# mt15_n.net
KiCad netlist of a schematic drawn in EAGLE
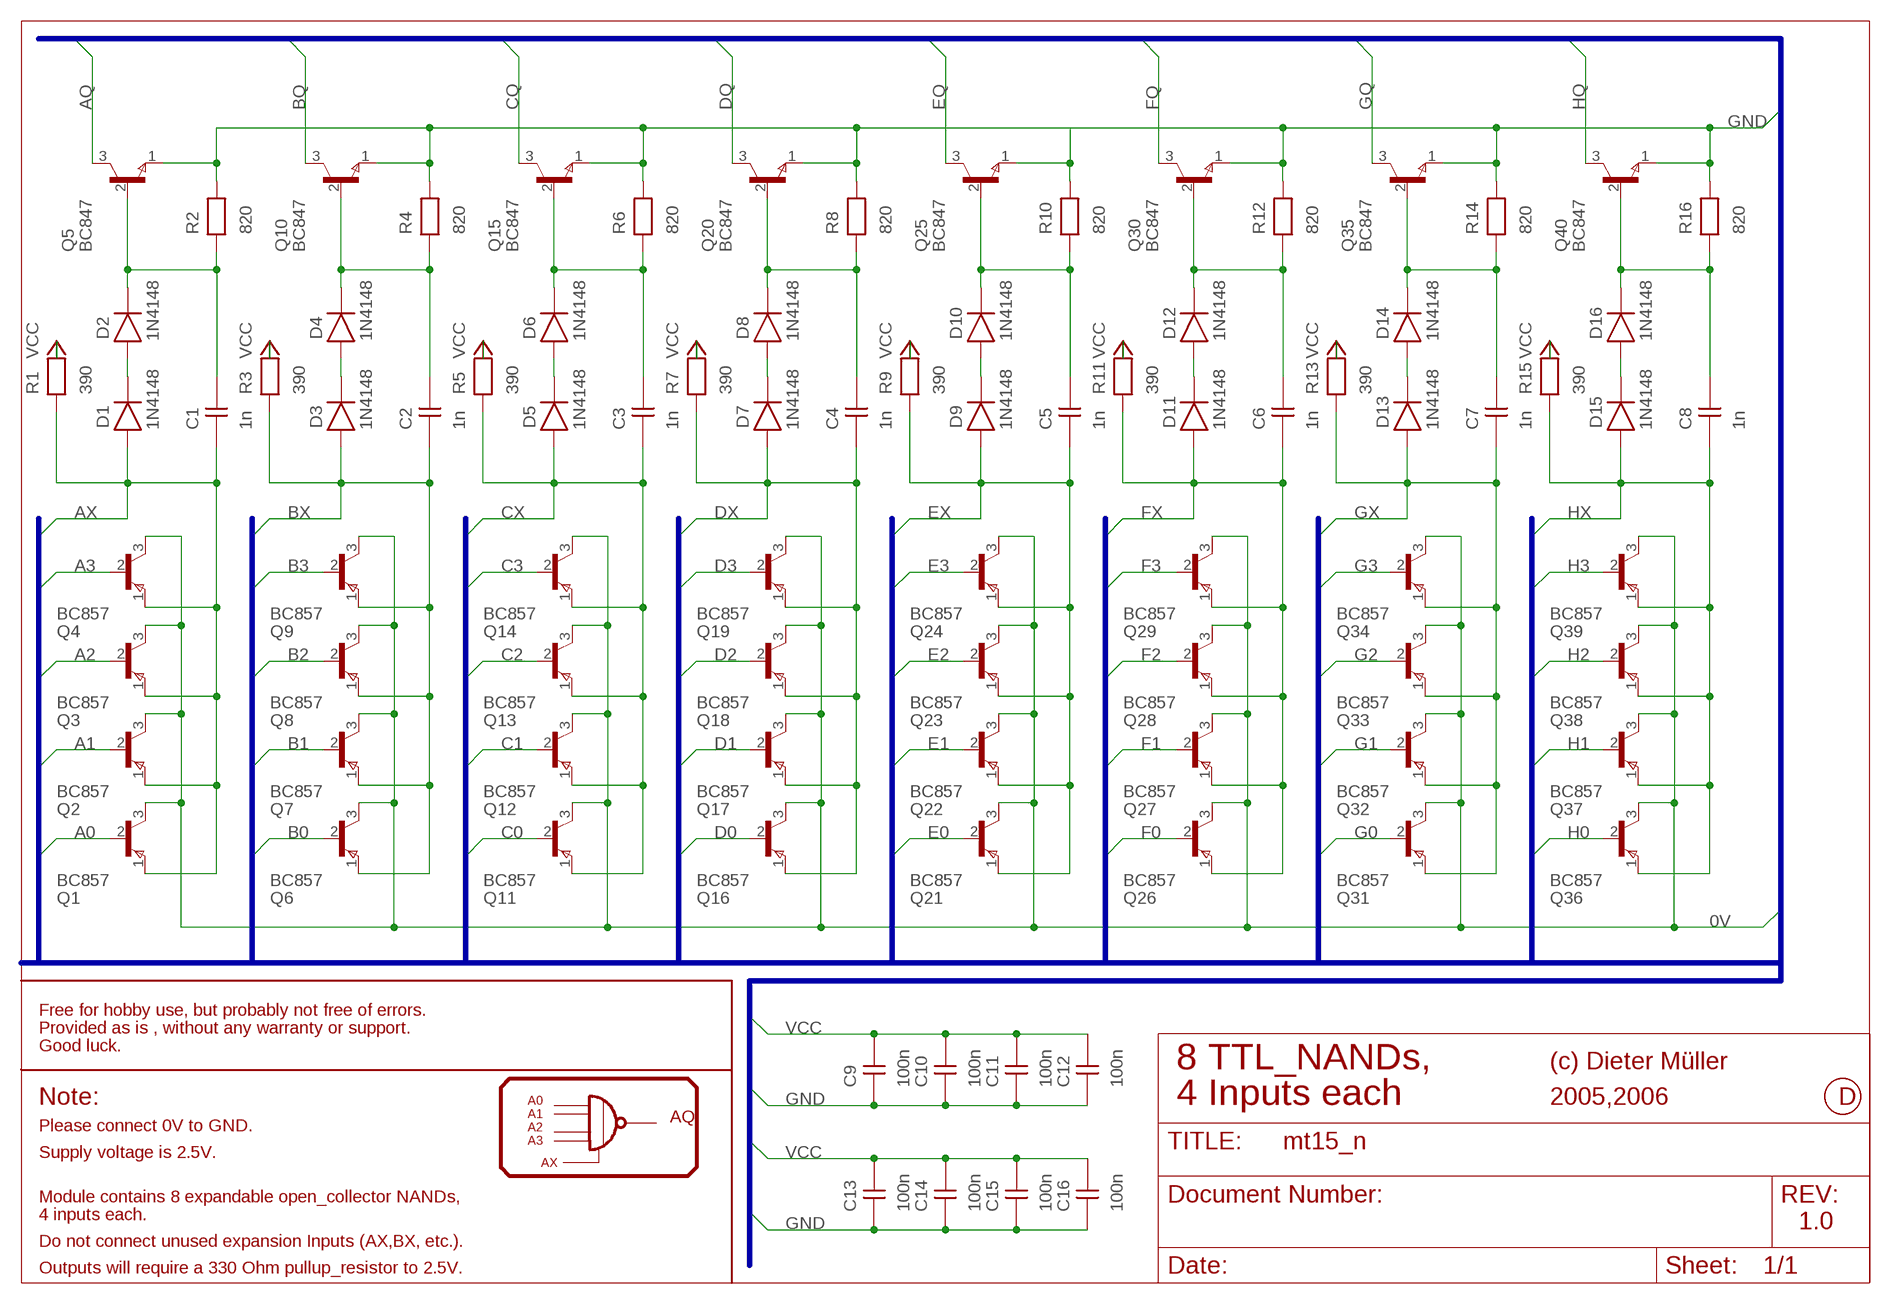
[diagram p0: schematic, sheet 1]

(export (version "E")
  (design (tool "Eeschema 10.0.6"))
  (components
    (comp (ref "C1")
      (value "1n")
      (footprint "eagle-import:0204")
      (libsource (lib "eagle-import") (part "CAPNP-5@2"))
    )
    (comp (ref "C2")
      (value "1n")
      (footprint "eagle-import:0204")
      (libsource (lib "eagle-import") (part "CAPNP-5@2"))
    )
    (comp (ref "C3")
      (value "1n")
      (footprint "eagle-import:0204")
      (libsource (lib "eagle-import") (part "CAPNP-5@2"))
    )
    (comp (ref "C4")
      (value "1n")
      (footprint "eagle-import:0204")
      (libsource (lib "eagle-import") (part "CAPNP-5@2"))
    )
    (comp (ref "C5")
      (value "1n")
      (footprint "eagle-import:0204")
      (libsource (lib "eagle-import") (part "CAPNP-5@2"))
    )
    (comp (ref "C6")
      (value "1n")
      (footprint "eagle-import:0204")
      (libsource (lib "eagle-import") (part "CAPNP-5@2"))
    )
    (comp (ref "C7")
      (value "1n")
      (footprint "eagle-import:0204")
      (libsource (lib "eagle-import") (part "CAPNP-5@2"))
    )
    (comp (ref "C8")
      (value "1n")
      (footprint "eagle-import:0204")
      (libsource (lib "eagle-import") (part "CAPNP-5@2"))
    )
    (comp (ref "C9")
      (value "100n")
      (footprint "eagle-import:0204")
      (libsource (lib "eagle-import") (part "CAPNP-5@2"))
    )
    (comp (ref "C10")
      (value "100n")
      (footprint "eagle-import:0204")
      (libsource (lib "eagle-import") (part "CAPNP-5@2"))
    )
    (comp (ref "C11")
      (value "100n")
      (footprint "eagle-import:0204")
      (libsource (lib "eagle-import") (part "CAPNP-5@2"))
    )
    (comp (ref "C12")
      (value "100n")
      (footprint "eagle-import:0204")
      (libsource (lib "eagle-import") (part "CAPNP-5@2"))
    )
    (comp (ref "C13")
      (value "100n")
      (footprint "eagle-import:0204")
      (libsource (lib "eagle-import") (part "CAPNP-5@2"))
    )
    (comp (ref "C14")
      (value "100n")
      (footprint "eagle-import:0204")
      (libsource (lib "eagle-import") (part "CAPNP-5@2"))
    )
    (comp (ref "C15")
      (value "100n")
      (footprint "eagle-import:0204")
      (libsource (lib "eagle-import") (part "CAPNP-5@2"))
    )
    (comp (ref "C16")
      (value "100n")
      (footprint "eagle-import:0204")
      (libsource (lib "eagle-import") (part "CAPNP-5@2"))
    )
    (comp (ref "D1")
      (value "1N4148")
      (footprint "eagle-import:0204D")
      (libsource (lib "eagle-import") (part "DIODE-7,5@2"))
    )
    (comp (ref "D2")
      (value "1N4148")
      (footprint "eagle-import:0204D")
      (libsource (lib "eagle-import") (part "DIODE-7,5@2"))
    )
    (comp (ref "D3")
      (value "1N4148")
      (footprint "eagle-import:0204D")
      (libsource (lib "eagle-import") (part "DIODE-7,5@2"))
    )
    (comp (ref "D4")
      (value "1N4148")
      (footprint "eagle-import:0204D")
      (libsource (lib "eagle-import") (part "DIODE-7,5@2"))
    )
    (comp (ref "D5")
      (value "1N4148")
      (footprint "eagle-import:0204D")
      (libsource (lib "eagle-import") (part "DIODE-7,5@2"))
    )
    (comp (ref "D6")
      (value "1N4148")
      (footprint "eagle-import:0204D")
      (libsource (lib "eagle-import") (part "DIODE-7,5@2"))
    )
    (comp (ref "D7")
      (value "1N4148")
      (footprint "eagle-import:0204D")
      (libsource (lib "eagle-import") (part "DIODE-7,5@2"))
    )
    (comp (ref "D8")
      (value "1N4148")
      (footprint "eagle-import:0204D")
      (libsource (lib "eagle-import") (part "DIODE-7,5@2"))
    )
    (comp (ref "D9")
      (value "1N4148")
      (footprint "eagle-import:0204D")
      (libsource (lib "eagle-import") (part "DIODE-7,5@2"))
    )
    (comp (ref "D10")
      (value "1N4148")
      (footprint "eagle-import:0204D")
      (libsource (lib "eagle-import") (part "DIODE-7,5@2"))
    )
    (comp (ref "D11")
      (value "1N4148")
      (footprint "eagle-import:0204D")
      (libsource (lib "eagle-import") (part "DIODE-7,5@2"))
    )
    (comp (ref "D12")
      (value "1N4148")
      (footprint "eagle-import:0204D")
      (libsource (lib "eagle-import") (part "DIODE-7,5@2"))
    )
    (comp (ref "D13")
      (value "1N4148")
      (footprint "eagle-import:0204D")
      (libsource (lib "eagle-import") (part "DIODE-7,5@2"))
    )
    (comp (ref "D14")
      (value "1N4148")
      (footprint "eagle-import:0204D")
      (libsource (lib "eagle-import") (part "DIODE-7,5@2"))
    )
    (comp (ref "D15")
      (value "1N4148")
      (footprint "eagle-import:0204D")
      (libsource (lib "eagle-import") (part "DIODE-7,5@2"))
    )
    (comp (ref "D16")
      (value "1N4148")
      (footprint "eagle-import:0204D")
      (libsource (lib "eagle-import") (part "DIODE-7,5@2"))
    )
    (comp (ref "Q1")
      (value "BC857")
      (footprint "eagle-import:SOT-23")
      (libsource (lib "eagle-import") (part "BC557@2"))
    )
    (comp (ref "Q2")
      (value "BC857")
      (footprint "eagle-import:SOT-23")
      (libsource (lib "eagle-import") (part "BC557@2"))
    )
    (comp (ref "Q3")
      (value "BC857")
      (footprint "eagle-import:SOT-23")
      (libsource (lib "eagle-import") (part "BC557@2"))
    )
    (comp (ref "Q4")
      (value "BC857")
      (footprint "eagle-import:SOT-23")
      (libsource (lib "eagle-import") (part "BC557@2"))
    )
    (comp (ref "Q5")
      (value "BC847")
      (footprint "eagle-import:SOT-23")
      (libsource (lib "eagle-import") (part "BC547@2"))
    )
    (comp (ref "Q6")
      (value "BC857")
      (footprint "eagle-import:SOT-23")
      (libsource (lib "eagle-import") (part "BC557@2"))
    )
    (comp (ref "Q7")
      (value "BC857")
      (footprint "eagle-import:SOT-23")
      (libsource (lib "eagle-import") (part "BC557@2"))
    )
    (comp (ref "Q8")
      (value "BC857")
      (footprint "eagle-import:SOT-23")
      (libsource (lib "eagle-import") (part "BC557@2"))
    )
    (comp (ref "Q9")
      (value "BC857")
      (footprint "eagle-import:SOT-23")
      (libsource (lib "eagle-import") (part "BC557@2"))
    )
    (comp (ref "Q10")
      (value "BC847")
      (footprint "eagle-import:SOT-23")
      (libsource (lib "eagle-import") (part "BC547@2"))
    )
    (comp (ref "Q11")
      (value "BC857")
      (footprint "eagle-import:SOT-23")
      (libsource (lib "eagle-import") (part "BC557@2"))
    )
    (comp (ref "Q12")
      (value "BC857")
      (footprint "eagle-import:SOT-23")
      (libsource (lib "eagle-import") (part "BC557@2"))
    )
    (comp (ref "Q13")
      (value "BC857")
      (footprint "eagle-import:SOT-23")
      (libsource (lib "eagle-import") (part "BC557@2"))
    )
    (comp (ref "Q14")
      (value "BC857")
      (footprint "eagle-import:SOT-23")
      (libsource (lib "eagle-import") (part "BC557@2"))
    )
    (comp (ref "Q15")
      (value "BC847")
      (footprint "eagle-import:SOT-23")
      (libsource (lib "eagle-import") (part "BC547@2"))
    )
    (comp (ref "Q16")
      (value "BC857")
      (footprint "eagle-import:SOT-23")
      (libsource (lib "eagle-import") (part "BC557@2"))
    )
    (comp (ref "Q17")
      (value "BC857")
      (footprint "eagle-import:SOT-23")
      (libsource (lib "eagle-import") (part "BC557@2"))
    )
    (comp (ref "Q18")
      (value "BC857")
      (footprint "eagle-import:SOT-23")
      (libsource (lib "eagle-import") (part "BC557@2"))
    )
    (comp (ref "Q19")
      (value "BC857")
      (footprint "eagle-import:SOT-23")
      (libsource (lib "eagle-import") (part "BC557@2"))
    )
    (comp (ref "Q20")
      (value "BC847")
      (footprint "eagle-import:SOT-23")
      (libsource (lib "eagle-import") (part "BC547@2"))
    )
    (comp (ref "Q21")
      (value "BC857")
      (footprint "eagle-import:SOT-23")
      (libsource (lib "eagle-import") (part "BC557@2"))
    )
    (comp (ref "Q22")
      (value "BC857")
      (footprint "eagle-import:SOT-23")
      (libsource (lib "eagle-import") (part "BC557@2"))
    )
    (comp (ref "Q23")
      (value "BC857")
      (footprint "eagle-import:SOT-23")
      (libsource (lib "eagle-import") (part "BC557@2"))
    )
    (comp (ref "Q24")
      (value "BC857")
      (footprint "eagle-import:SOT-23")
      (libsource (lib "eagle-import") (part "BC557@2"))
    )
    (comp (ref "Q25")
      (value "BC847")
      (footprint "eagle-import:SOT-23")
      (libsource (lib "eagle-import") (part "BC547@2"))
    )
    (comp (ref "Q26")
      (value "BC857")
      (footprint "eagle-import:SOT-23")
      (libsource (lib "eagle-import") (part "BC557@2"))
    )
    (comp (ref "Q27")
      (value "BC857")
      (footprint "eagle-import:SOT-23")
      (libsource (lib "eagle-import") (part "BC557@2"))
    )
    (comp (ref "Q28")
      (value "BC857")
      (footprint "eagle-import:SOT-23")
      (libsource (lib "eagle-import") (part "BC557@2"))
    )
    (comp (ref "Q29")
      (value "BC857")
      (footprint "eagle-import:SOT-23")
      (libsource (lib "eagle-import") (part "BC557@2"))
    )
    (comp (ref "Q30")
      (value "BC847")
      (footprint "eagle-import:SOT-23")
      (libsource (lib "eagle-import") (part "BC547@2"))
    )
    (comp (ref "Q31")
      (value "BC857")
      (footprint "eagle-import:SOT-23")
      (libsource (lib "eagle-import") (part "BC557@2"))
    )
    (comp (ref "Q32")
      (value "BC857")
      (footprint "eagle-import:SOT-23")
      (libsource (lib "eagle-import") (part "BC557@2"))
    )
    (comp (ref "Q33")
      (value "BC857")
      (footprint "eagle-import:SOT-23")
      (libsource (lib "eagle-import") (part "BC557@2"))
    )
    (comp (ref "Q34")
      (value "BC857")
      (footprint "eagle-import:SOT-23")
      (libsource (lib "eagle-import") (part "BC557@2"))
    )
    (comp (ref "Q35")
      (value "BC847")
      (footprint "eagle-import:SOT-23")
      (libsource (lib "eagle-import") (part "BC547@2"))
    )
    (comp (ref "Q36")
      (value "BC857")
      (footprint "eagle-import:SOT-23")
      (libsource (lib "eagle-import") (part "BC557@2"))
    )
    (comp (ref "Q37")
      (value "BC857")
      (footprint "eagle-import:SOT-23")
      (libsource (lib "eagle-import") (part "BC557@2"))
    )
    (comp (ref "Q38")
      (value "BC857")
      (footprint "eagle-import:SOT-23")
      (libsource (lib "eagle-import") (part "BC557@2"))
    )
    (comp (ref "Q39")
      (value "BC857")
      (footprint "eagle-import:SOT-23")
      (libsource (lib "eagle-import") (part "BC557@2"))
    )
    (comp (ref "Q40")
      (value "BC847")
      (footprint "eagle-import:SOT-23")
      (libsource (lib "eagle-import") (part "BC547@2"))
    )
    (comp (ref "R1")
      (value "390")
      (footprint "eagle-import:0204")
      (libsource (lib "eagle-import") (part "RESEU-7,5@2"))
    )
    (comp (ref "R2")
      (value "820")
      (footprint "eagle-import:0204")
      (libsource (lib "eagle-import") (part "RESEU-7,5@2"))
    )
    (comp (ref "R3")
      (value "390")
      (footprint "eagle-import:0204")
      (libsource (lib "eagle-import") (part "RESEU-7,5@2"))
    )
    (comp (ref "R4")
      (value "820")
      (footprint "eagle-import:0204")
      (libsource (lib "eagle-import") (part "RESEU-7,5@2"))
    )
    (comp (ref "R5")
      (value "390")
      (footprint "eagle-import:0204")
      (libsource (lib "eagle-import") (part "RESEU-7,5@2"))
    )
    (comp (ref "R6")
      (value "820")
      (footprint "eagle-import:0204")
      (libsource (lib "eagle-import") (part "RESEU-7,5@2"))
    )
    (comp (ref "R7")
      (value "390")
      (footprint "eagle-import:0204")
      (libsource (lib "eagle-import") (part "RESEU-7,5@2"))
    )
    (comp (ref "R8")
      (value "820")
      (footprint "eagle-import:0204")
      (libsource (lib "eagle-import") (part "RESEU-7,5@2"))
    )
    (comp (ref "R9")
      (value "390")
      (footprint "eagle-import:0204")
      (libsource (lib "eagle-import") (part "RESEU-7,5@2"))
    )
    (comp (ref "R10")
      (value "820")
      (footprint "eagle-import:0204")
      (libsource (lib "eagle-import") (part "RESEU-7,5@2"))
    )
    (comp (ref "R11")
      (value "390")
      (footprint "eagle-import:0204")
      (libsource (lib "eagle-import") (part "RESEU-7,5@2"))
    )
    (comp (ref "R12")
      (value "820")
      (footprint "eagle-import:0204")
      (libsource (lib "eagle-import") (part "RESEU-7,5@2"))
    )
    (comp (ref "R13")
      (value "390")
      (footprint "eagle-import:0204")
      (libsource (lib "eagle-import") (part "RESEU-7,5@2"))
    )
    (comp (ref "R14")
      (value "820")
      (footprint "eagle-import:0204")
      (libsource (lib "eagle-import") (part "RESEU-7,5@2"))
    )
    (comp (ref "R15")
      (value "390")
      (footprint "eagle-import:0204")
      (libsource (lib "eagle-import") (part "RESEU-7,5@2"))
    )
    (comp (ref "R16")
      (value "820")
      (footprint "eagle-import:0204")
      (libsource (lib "eagle-import") (part "RESEU-7,5@2"))
    )
  )
  (nets
    (net (code "2") (name "/0V") (class "Default")
      (node (ref "Q1") (pin "3") (pinfunction "C_3") (pintype "passive"))
      (node (ref "Q11") (pin "3") (pinfunction "C_3") (pintype "passive"))
      (node (ref "Q12") (pin "3") (pinfunction "C_3") (pintype "passive"))
      (node (ref "Q13") (pin "3") (pinfunction "C_3") (pintype "passive"))
      (node (ref "Q14") (pin "3") (pinfunction "C_3") (pintype "passive"))
      (node (ref "Q16") (pin "3") (pinfunction "C_3") (pintype "passive"))
      (node (ref "Q17") (pin "3") (pinfunction "C_3") (pintype "passive"))
      (node (ref "Q18") (pin "3") (pinfunction "C_3") (pintype "passive"))
      (node (ref "Q19") (pin "3") (pinfunction "C_3") (pintype "passive"))
      (node (ref "Q2") (pin "3") (pinfunction "C_3") (pintype "passive"))
      (node (ref "Q21") (pin "3") (pinfunction "C_3") (pintype "passive"))
      (node (ref "Q22") (pin "3") (pinfunction "C_3") (pintype "passive"))
      (node (ref "Q23") (pin "3") (pinfunction "C_3") (pintype "passive"))
      (node (ref "Q24") (pin "3") (pinfunction "C_3") (pintype "passive"))
      (node (ref "Q26") (pin "3") (pinfunction "C_3") (pintype "passive"))
      (node (ref "Q27") (pin "3") (pinfunction "C_3") (pintype "passive"))
      (node (ref "Q28") (pin "3") (pinfunction "C_3") (pintype "passive"))
      (node (ref "Q29") (pin "3") (pinfunction "C_3") (pintype "passive"))
      (node (ref "Q3") (pin "3") (pinfunction "C_3") (pintype "passive"))
      (node (ref "Q31") (pin "3") (pinfunction "C_3") (pintype "passive"))
      (node (ref "Q32") (pin "3") (pinfunction "C_3") (pintype "passive"))
      (node (ref "Q33") (pin "3") (pinfunction "C_3") (pintype "passive"))
      (node (ref "Q34") (pin "3") (pinfunction "C_3") (pintype "passive"))
      (node (ref "Q36") (pin "3") (pinfunction "C_3") (pintype "passive"))
      (node (ref "Q37") (pin "3") (pinfunction "C_3") (pintype "passive"))
      (node (ref "Q38") (pin "3") (pinfunction "C_3") (pintype "passive"))
      (node (ref "Q39") (pin "3") (pinfunction "C_3") (pintype "passive"))
      (node (ref "Q4") (pin "3") (pinfunction "C_3") (pintype "passive"))
      (node (ref "Q6") (pin "3") (pinfunction "C_3") (pintype "passive"))
      (node (ref "Q7") (pin "3") (pinfunction "C_3") (pintype "passive"))
      (node (ref "Q8") (pin "3") (pinfunction "C_3") (pintype "passive"))
      (node (ref "Q9") (pin "3") (pinfunction "C_3") (pintype "passive"))
    )
    (net (code "3") (name "/A0") (class "Default")
      (node (ref "Q1") (pin "2") (pinfunction "B_2") (pintype "passive"))
    )
    (net (code "4") (name "/A1") (class "Default")
      (node (ref "Q2") (pin "2") (pinfunction "B_2") (pintype "passive"))
    )
    (net (code "5") (name "/A2") (class "Default")
      (node (ref "Q3") (pin "2") (pinfunction "B_2") (pintype "passive"))
    )
    (net (code "6") (name "/A3") (class "Default")
      (node (ref "Q4") (pin "2") (pinfunction "B_2") (pintype "passive"))
    )
    (net (code "7") (name "/AQ") (class "Default")
      (node (ref "Q5") (pin "3") (pinfunction "C_3") (pintype "passive"))
    )
    (net (code "8") (name "/AX") (class "Default")
      (node (ref "C1") (pin "1") (pinfunction "1_1") (pintype "passive"))
      (node (ref "D1") (pin "1") (pinfunction "A_1") (pintype "passive"))
      (node (ref "Q1") (pin "1") (pinfunction "E_1") (pintype "passive"))
      (node (ref "Q2") (pin "1") (pinfunction "E_1") (pintype "passive"))
      (node (ref "Q3") (pin "1") (pinfunction "E_1") (pintype "passive"))
      (node (ref "Q4") (pin "1") (pinfunction "E_1") (pintype "passive"))
      (node (ref "R1") (pin "1") (pinfunction "1_1") (pintype "passive"))
    )
    (net (code "9") (name "/B0") (class "Default")
      (node (ref "Q6") (pin "2") (pinfunction "B_2") (pintype "passive"))
    )
    (net (code "10") (name "/B1") (class "Default")
      (node (ref "Q7") (pin "2") (pinfunction "B_2") (pintype "passive"))
    )
    (net (code "11") (name "/B2") (class "Default")
      (node (ref "Q8") (pin "2") (pinfunction "B_2") (pintype "passive"))
    )
    (net (code "12") (name "/B3") (class "Default")
      (node (ref "Q9") (pin "2") (pinfunction "B_2") (pintype "passive"))
    )
    (net (code "13") (name "/BQ") (class "Default")
      (node (ref "Q10") (pin "3") (pinfunction "C_3") (pintype "passive"))
    )
    (net (code "14") (name "/BX") (class "Default")
      (node (ref "C2") (pin "1") (pinfunction "1_1") (pintype "passive"))
      (node (ref "D3") (pin "1") (pinfunction "A_1") (pintype "passive"))
      (node (ref "Q6") (pin "1") (pinfunction "E_1") (pintype "passive"))
      (node (ref "Q7") (pin "1") (pinfunction "E_1") (pintype "passive"))
      (node (ref "Q8") (pin "1") (pinfunction "E_1") (pintype "passive"))
      (node (ref "Q9") (pin "1") (pinfunction "E_1") (pintype "passive"))
      (node (ref "R3") (pin "1") (pinfunction "1_1") (pintype "passive"))
    )
    (net (code "15") (name "/C0") (class "Default")
      (node (ref "Q11") (pin "2") (pinfunction "B_2") (pintype "passive"))
    )
    (net (code "16") (name "/C1") (class "Default")
      (node (ref "Q12") (pin "2") (pinfunction "B_2") (pintype "passive"))
    )
    (net (code "17") (name "/C2") (class "Default")
      (node (ref "Q13") (pin "2") (pinfunction "B_2") (pintype "passive"))
    )
    (net (code "18") (name "/C3") (class "Default")
      (node (ref "Q14") (pin "2") (pinfunction "B_2") (pintype "passive"))
    )
    (net (code "19") (name "/CQ") (class "Default")
      (node (ref "Q15") (pin "3") (pinfunction "C_3") (pintype "passive"))
    )
    (net (code "20") (name "/CX") (class "Default")
      (node (ref "C3") (pin "1") (pinfunction "1_1") (pintype "passive"))
      (node (ref "D5") (pin "1") (pinfunction "A_1") (pintype "passive"))
      (node (ref "Q11") (pin "1") (pinfunction "E_1") (pintype "passive"))
      (node (ref "Q12") (pin "1") (pinfunction "E_1") (pintype "passive"))
      (node (ref "Q13") (pin "1") (pinfunction "E_1") (pintype "passive"))
      (node (ref "Q14") (pin "1") (pinfunction "E_1") (pintype "passive"))
      (node (ref "R5") (pin "1") (pinfunction "1_1") (pintype "passive"))
    )
    (net (code "21") (name "/D0") (class "Default")
      (node (ref "Q16") (pin "2") (pinfunction "B_2") (pintype "passive"))
    )
    (net (code "22") (name "/D1") (class "Default")
      (node (ref "Q17") (pin "2") (pinfunction "B_2") (pintype "passive"))
    )
    (net (code "23") (name "/D2") (class "Default")
      (node (ref "Q18") (pin "2") (pinfunction "B_2") (pintype "passive"))
    )
    (net (code "24") (name "/D3") (class "Default")
      (node (ref "Q19") (pin "2") (pinfunction "B_2") (pintype "passive"))
    )
    (net (code "25") (name "/DQ") (class "Default")
      (node (ref "Q20") (pin "3") (pinfunction "C_3") (pintype "passive"))
    )
    (net (code "26") (name "/DX") (class "Default")
      (node (ref "C4") (pin "1") (pinfunction "1_1") (pintype "passive"))
      (node (ref "D7") (pin "1") (pinfunction "A_1") (pintype "passive"))
      (node (ref "Q16") (pin "1") (pinfunction "E_1") (pintype "passive"))
      (node (ref "Q17") (pin "1") (pinfunction "E_1") (pintype "passive"))
      (node (ref "Q18") (pin "1") (pinfunction "E_1") (pintype "passive"))
      (node (ref "Q19") (pin "1") (pinfunction "E_1") (pintype "passive"))
      (node (ref "R7") (pin "1") (pinfunction "1_1") (pintype "passive"))
    )
    (net (code "27") (name "/E0") (class "Default")
      (node (ref "Q21") (pin "2") (pinfunction "B_2") (pintype "passive"))
    )
    (net (code "28") (name "/E1") (class "Default")
      (node (ref "Q22") (pin "2") (pinfunction "B_2") (pintype "passive"))
    )
    (net (code "29") (name "/E2") (class "Default")
      (node (ref "Q23") (pin "2") (pinfunction "B_2") (pintype "passive"))
    )
    (net (code "30") (name "/E3") (class "Default")
      (node (ref "Q24") (pin "2") (pinfunction "B_2") (pintype "passive"))
    )
    (net (code "31") (name "/EQ") (class "Default")
      (node (ref "Q25") (pin "3") (pinfunction "C_3") (pintype "passive"))
    )
    (net (code "32") (name "/EX") (class "Default")
      (node (ref "C5") (pin "1") (pinfunction "1_1") (pintype "passive"))
      (node (ref "D9") (pin "1") (pinfunction "A_1") (pintype "passive"))
      (node (ref "Q21") (pin "1") (pinfunction "E_1") (pintype "passive"))
      (node (ref "Q22") (pin "1") (pinfunction "E_1") (pintype "passive"))
      (node (ref "Q23") (pin "1") (pinfunction "E_1") (pintype "passive"))
      (node (ref "Q24") (pin "1") (pinfunction "E_1") (pintype "passive"))
      (node (ref "R9") (pin "1") (pinfunction "1_1") (pintype "passive"))
    )
    (net (code "33") (name "/F0") (class "Default")
      (node (ref "Q26") (pin "2") (pinfunction "B_2") (pintype "passive"))
    )
    (net (code "34") (name "/F1") (class "Default")
      (node (ref "Q27") (pin "2") (pinfunction "B_2") (pintype "passive"))
    )
    (net (code "35") (name "/F2") (class "Default")
      (node (ref "Q28") (pin "2") (pinfunction "B_2") (pintype "passive"))
    )
    (net (code "36") (name "/F3") (class "Default")
      (node (ref "Q29") (pin "2") (pinfunction "B_2") (pintype "passive"))
    )
    (net (code "37") (name "/FQ") (class "Default")
      (node (ref "Q30") (pin "3") (pinfunction "C_3") (pintype "passive"))
    )
    (net (code "38") (name "/FX") (class "Default")
      (node (ref "C6") (pin "1") (pinfunction "1_1") (pintype "passive"))
      (node (ref "D11") (pin "1") (pinfunction "A_1") (pintype "passive"))
      (node (ref "Q26") (pin "1") (pinfunction "E_1") (pintype "passive"))
      (node (ref "Q27") (pin "1") (pinfunction "E_1") (pintype "passive"))
      (node (ref "Q28") (pin "1") (pinfunction "E_1") (pintype "passive"))
      (node (ref "Q29") (pin "1") (pinfunction "E_1") (pintype "passive"))
      (node (ref "R11") (pin "1") (pinfunction "1_1") (pintype "passive"))
    )
    (net (code "39") (name "/G0") (class "Default")
      (node (ref "Q31") (pin "2") (pinfunction "B_2") (pintype "passive"))
    )
    (net (code "40") (name "/G1") (class "Default")
      (node (ref "Q32") (pin "2") (pinfunction "B_2") (pintype "passive"))
    )
    (net (code "41") (name "/G2") (class "Default")
      (node (ref "Q33") (pin "2") (pinfunction "B_2") (pintype "passive"))
    )
    (net (code "42") (name "/G3") (class "Default")
      (node (ref "Q34") (pin "2") (pinfunction "B_2") (pintype "passive"))
    )
    (net (code "43") (name "/GND") (class "Default")
      (node (ref "C10") (pin "1") (pinfunction "1_1") (pintype "passive"))
      (node (ref "C11") (pin "1") (pinfunction "1_1") (pintype "passive"))
      (node (ref "C12") (pin "1") (pinfunction "1_1") (pintype "passive"))
      (node (ref "C13") (pin "1") (pinfunction "1_1") (pintype "passive"))
      (node (ref "C14") (pin "1") (pinfunction "1_1") (pintype "passive"))
      (node (ref "C15") (pin "1") (pinfunction "1_1") (pintype "passive"))
      (node (ref "C16") (pin "1") (pinfunction "1_1") (pintype "passive"))
      (node (ref "C9") (pin "1") (pinfunction "1_1") (pintype "passive"))
      (node (ref "Q10") (pin "1") (pinfunction "E_1") (pintype "passive"))
      (node (ref "Q15") (pin "1") (pinfunction "E_1") (pintype "passive"))
      (node (ref "Q20") (pin "1") (pinfunction "E_1") (pintype "passive"))
      (node (ref "Q25") (pin "1") (pinfunction "E_1") (pintype "passive"))
      (node (ref "Q30") (pin "1") (pinfunction "E_1") (pintype "passive"))
      (node (ref "Q35") (pin "1") (pinfunction "E_1") (pintype "passive"))
      (node (ref "Q40") (pin "1") (pinfunction "E_1") (pintype "passive"))
      (node (ref "Q5") (pin "1") (pinfunction "E_1") (pintype "passive"))
      (node (ref "R10") (pin "2") (pinfunction "2_2") (pintype "passive"))
      (node (ref "R12") (pin "2") (pinfunction "2_2") (pintype "passive"))
      (node (ref "R14") (pin "2") (pinfunction "2_2") (pintype "passive"))
      (node (ref "R16") (pin "2") (pinfunction "2_2") (pintype "passive"))
      (node (ref "R2") (pin "2") (pinfunction "2_2") (pintype "passive"))
      (node (ref "R4") (pin "2") (pinfunction "2_2") (pintype "passive"))
      (node (ref "R6") (pin "2") (pinfunction "2_2") (pintype "passive"))
      (node (ref "R8") (pin "2") (pinfunction "2_2") (pintype "passive"))
    )
    (net (code "44") (name "/GQ") (class "Default")
      (node (ref "Q35") (pin "3") (pinfunction "C_3") (pintype "passive"))
    )
    (net (code "45") (name "/GX") (class "Default")
      (node (ref "C7") (pin "1") (pinfunction "1_1") (pintype "passive"))
      (node (ref "D13") (pin "1") (pinfunction "A_1") (pintype "passive"))
      (node (ref "Q31") (pin "1") (pinfunction "E_1") (pintype "passive"))
      (node (ref "Q32") (pin "1") (pinfunction "E_1") (pintype "passive"))
      (node (ref "Q33") (pin "1") (pinfunction "E_1") (pintype "passive"))
      (node (ref "Q34") (pin "1") (pinfunction "E_1") (pintype "passive"))
      (node (ref "R13") (pin "1") (pinfunction "1_1") (pintype "passive"))
    )
    (net (code "46") (name "/H0") (class "Default")
      (node (ref "Q36") (pin "2") (pinfunction "B_2") (pintype "passive"))
    )
    (net (code "47") (name "/H1") (class "Default")
      (node (ref "Q37") (pin "2") (pinfunction "B_2") (pintype "passive"))
    )
    (net (code "48") (name "/H2") (class "Default")
      (node (ref "Q38") (pin "2") (pinfunction "B_2") (pintype "passive"))
    )
    (net (code "49") (name "/H3") (class "Default")
      (node (ref "Q39") (pin "2") (pinfunction "B_2") (pintype "passive"))
    )
    (net (code "50") (name "/HQ") (class "Default")
      (node (ref "Q40") (pin "3") (pinfunction "C_3") (pintype "passive"))
    )
    (net (code "51") (name "/HX") (class "Default")
      (node (ref "C8") (pin "1") (pinfunction "1_1") (pintype "passive"))
      (node (ref "D15") (pin "1") (pinfunction "A_1") (pintype "passive"))
      (node (ref "Q36") (pin "1") (pinfunction "E_1") (pintype "passive"))
      (node (ref "Q37") (pin "1") (pinfunction "E_1") (pintype "passive"))
      (node (ref "Q38") (pin "1") (pinfunction "E_1") (pintype "passive"))
      (node (ref "Q39") (pin "1") (pinfunction "E_1") (pintype "passive"))
      (node (ref "R15") (pin "1") (pinfunction "1_1") (pintype "passive"))
    )
    (net (code "53") (name "Net-(D1-K)") (class "Default")
      (node (ref "D1") (pin "2") (pinfunction "K_2") (pintype "passive"))
      (node (ref "D2") (pin "1") (pinfunction "A_1") (pintype "passive"))
    )
    (net (code "54") (name "Net-(D2-K)") (class "Default")
      (node (ref "C1") (pin "2") (pinfunction "2_2") (pintype "passive"))
      (node (ref "D2") (pin "2") (pinfunction "K_2") (pintype "passive"))
      (node (ref "Q5") (pin "2") (pinfunction "B_2") (pintype "passive"))
      (node (ref "R2") (pin "1") (pinfunction "1_1") (pintype "passive"))
    )
    (net (code "55") (name "Net-(D3-K)") (class "Default")
      (node (ref "D3") (pin "2") (pinfunction "K_2") (pintype "passive"))
      (node (ref "D4") (pin "1") (pinfunction "A_1") (pintype "passive"))
    )
    (net (code "56") (name "Net-(D4-K)") (class "Default")
      (node (ref "C2") (pin "2") (pinfunction "2_2") (pintype "passive"))
      (node (ref "D4") (pin "2") (pinfunction "K_2") (pintype "passive"))
      (node (ref "Q10") (pin "2") (pinfunction "B_2") (pintype "passive"))
      (node (ref "R4") (pin "1") (pinfunction "1_1") (pintype "passive"))
    )
    (net (code "57") (name "Net-(D5-K)") (class "Default")
      (node (ref "D5") (pin "2") (pinfunction "K_2") (pintype "passive"))
      (node (ref "D6") (pin "1") (pinfunction "A_1") (pintype "passive"))
    )
    (net (code "58") (name "Net-(D6-K)") (class "Default")
      (node (ref "C3") (pin "2") (pinfunction "2_2") (pintype "passive"))
      (node (ref "D6") (pin "2") (pinfunction "K_2") (pintype "passive"))
      (node (ref "Q15") (pin "2") (pinfunction "B_2") (pintype "passive"))
      (node (ref "R6") (pin "1") (pinfunction "1_1") (pintype "passive"))
    )
    (net (code "59") (name "Net-(D7-K)") (class "Default")
      (node (ref "D7") (pin "2") (pinfunction "K_2") (pintype "passive"))
      (node (ref "D8") (pin "1") (pinfunction "A_1") (pintype "passive"))
    )
    (net (code "60") (name "Net-(D8-K)") (class "Default")
      (node (ref "C4") (pin "2") (pinfunction "2_2") (pintype "passive"))
      (node (ref "D8") (pin "2") (pinfunction "K_2") (pintype "passive"))
      (node (ref "Q20") (pin "2") (pinfunction "B_2") (pintype "passive"))
      (node (ref "R8") (pin "1") (pinfunction "1_1") (pintype "passive"))
    )
    (net (code "61") (name "Net-(D10-A)") (class "Default")
      (node (ref "D10") (pin "1") (pinfunction "A_1") (pintype "passive"))
      (node (ref "D9") (pin "2") (pinfunction "K_2") (pintype "passive"))
    )
    (net (code "62") (name "Net-(D10-K)") (class "Default")
      (node (ref "C5") (pin "2") (pinfunction "2_2") (pintype "passive"))
      (node (ref "D10") (pin "2") (pinfunction "K_2") (pintype "passive"))
      (node (ref "Q25") (pin "2") (pinfunction "B_2") (pintype "passive"))
      (node (ref "R10") (pin "1") (pinfunction "1_1") (pintype "passive"))
    )
    (net (code "63") (name "Net-(D11-K)") (class "Default")
      (node (ref "D11") (pin "2") (pinfunction "K_2") (pintype "passive"))
      (node (ref "D12") (pin "1") (pinfunction "A_1") (pintype "passive"))
    )
    (net (code "64") (name "Net-(D12-K)") (class "Default")
      (node (ref "C6") (pin "2") (pinfunction "2_2") (pintype "passive"))
      (node (ref "D12") (pin "2") (pinfunction "K_2") (pintype "passive"))
      (node (ref "Q30") (pin "2") (pinfunction "B_2") (pintype "passive"))
      (node (ref "R12") (pin "1") (pinfunction "1_1") (pintype "passive"))
    )
    (net (code "65") (name "Net-(D13-K)") (class "Default")
      (node (ref "D13") (pin "2") (pinfunction "K_2") (pintype "passive"))
      (node (ref "D14") (pin "1") (pinfunction "A_1") (pintype "passive"))
    )
    (net (code "66") (name "Net-(D14-K)") (class "Default")
      (node (ref "C7") (pin "2") (pinfunction "2_2") (pintype "passive"))
      (node (ref "D14") (pin "2") (pinfunction "K_2") (pintype "passive"))
      (node (ref "Q35") (pin "2") (pinfunction "B_2") (pintype "passive"))
      (node (ref "R14") (pin "1") (pinfunction "1_1") (pintype "passive"))
    )
    (net (code "67") (name "Net-(D15-K)") (class "Default")
      (node (ref "D15") (pin "2") (pinfunction "K_2") (pintype "passive"))
      (node (ref "D16") (pin "1") (pinfunction "A_1") (pintype "passive"))
    )
    (net (code "68") (name "Net-(D16-K)") (class "Default")
      (node (ref "C8") (pin "2") (pinfunction "2_2") (pintype "passive"))
      (node (ref "D16") (pin "2") (pinfunction "K_2") (pintype "passive"))
      (node (ref "Q40") (pin "2") (pinfunction "B_2") (pintype "passive"))
      (node (ref "R16") (pin "1") (pinfunction "1_1") (pintype "passive"))
    )
    (net (code "69") (name "VCC") (class "Default")
      (node (ref "C10") (pin "2") (pinfunction "2_2") (pintype "passive"))
      (node (ref "C11") (pin "2") (pinfunction "2_2") (pintype "passive"))
      (node (ref "C12") (pin "2") (pinfunction "2_2") (pintype "passive"))
      (node (ref "C13") (pin "2") (pinfunction "2_2") (pintype "passive"))
      (node (ref "C14") (pin "2") (pinfunction "2_2") (pintype "passive"))
      (node (ref "C15") (pin "2") (pinfunction "2_2") (pintype "passive"))
      (node (ref "C16") (pin "2") (pinfunction "2_2") (pintype "passive"))
      (node (ref "C9") (pin "2") (pinfunction "2_2") (pintype "passive"))
      (node (ref "R1") (pin "2") (pinfunction "2_2") (pintype "passive"))
      (node (ref "R11") (pin "2") (pinfunction "2_2") (pintype "passive"))
      (node (ref "R13") (pin "2") (pinfunction "2_2") (pintype "passive"))
      (node (ref "R15") (pin "2") (pinfunction "2_2") (pintype "passive"))
      (node (ref "R3") (pin "2") (pinfunction "2_2") (pintype "passive"))
      (node (ref "R5") (pin "2") (pinfunction "2_2") (pintype "passive"))
      (node (ref "R7") (pin "2") (pinfunction "2_2") (pintype "passive"))
      (node (ref "R9") (pin "2") (pinfunction "2_2") (pintype "passive"))
    )
  )
)
